# Durchgangspr_fer11.net
KiCad netlist of a schematic drawn in EAGLE
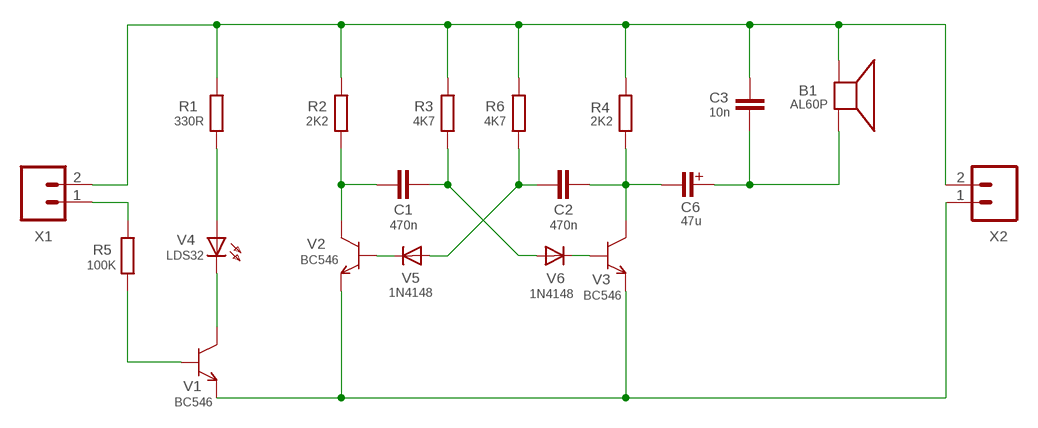
[diagram p0: schematic, sheet 1]

(export (version "E")
  (design (tool "Eeschema 10.0.6"))
  (components
    (comp (ref "B1")
      (value "AL60P")
      (footprint "eagle-import:AL60P")
      (libsource (lib "eagle-import") (part "AL60P"))
    )
    (comp (ref "C1")
      (value "470n")
      (footprint "eagle-import:C050-024X044")
      (libsource (lib "eagle-import") (part "C-EUC05-024X044"))
    )
    (comp (ref "C2")
      (value "470n")
      (footprint "eagle-import:C050-024X044")
      (libsource (lib "eagle-import") (part "C-EUC05-024X044"))
    )
    (comp (ref "C3")
      (value "10n")
      (footprint "eagle-import:C050-024X044")
      (libsource (lib "eagle-import") (part "C-EUC05-024X044"))
    )
    (comp (ref "C6")
      (value "47u")
      (footprint "eagle-import:E2,5-6")
      (libsource (lib "eagle-import") (part "CPOL-EUE2.5-6"))
    )
    (comp (ref "R1")
      (value "330R")
      (footprint "eagle-import:0207_10")
      (libsource (lib "eagle-import") (part "R-EU_0207/10"))
    )
    (comp (ref "R2")
      (value "2K2")
      (footprint "eagle-import:0207_10")
      (libsource (lib "eagle-import") (part "R-EU_0207/10"))
    )
    (comp (ref "R3")
      (value "4K7")
      (footprint "eagle-import:0207_10")
      (libsource (lib "eagle-import") (part "R-EU_0207/10"))
    )
    (comp (ref "R4")
      (value "2K2")
      (footprint "eagle-import:0207_10")
      (libsource (lib "eagle-import") (part "R-EU_0207/10"))
    )
    (comp (ref "R5")
      (value "100K")
      (footprint "eagle-import:0207_10")
      (libsource (lib "eagle-import") (part "R-EU_0207/10"))
    )
    (comp (ref "R6")
      (value "4K7")
      (footprint "eagle-import:0207_10")
      (libsource (lib "eagle-import") (part "R-EU_0207/10"))
    )
    (comp (ref "V1")
      (value "BC546")
      (footprint "eagle-import:TO92IL")
      (libsource (lib "eagle-import") (part "NPN_EBCBC546"))
    )
    (comp (ref "V2")
      (value "BC546")
      (footprint "eagle-import:TO92IL")
      (libsource (lib "eagle-import") (part "NPN_EBCBC546"))
    )
    (comp (ref "V3")
      (value "BC546")
      (footprint "eagle-import:TO92IL")
      (libsource (lib "eagle-import") (part "NPN_EBCBC546"))
    )
    (comp (ref "V4")
      (value "LDS32")
      (footprint "eagle-import:LED5")
      (libsource (lib "eagle-import") (part "LED5MM"))
    )
    (comp (ref "V5")
      (value "1N4148")
      (footprint "eagle-import:D7_5")
      (libsource (lib "eagle-import") (part "DIODE7_5"))
    )
    (comp (ref "V6")
      (value "1N4148")
      (footprint "eagle-import:D7_5")
      (libsource (lib "eagle-import") (part "DIODE7_5"))
    )
    (comp (ref "X1")
      (value "M02")
      (footprint "eagle-import:02P")
      (libsource (lib "eagle-import") (part "M02"))
    )
    (comp (ref "X2")
      (value "M02")
      (footprint "eagle-import:02P")
      (libsource (lib "eagle-import") (part "M02"))
    )
  )
  (nets
    (net (code "1") (name "Net-(B1-Pad1)") (class "Default")
      (node (ref "B1") (pin "1") (pinfunction "1_1") (pintype "passive"))
      (node (ref "C3") (pin "1") (pinfunction "1_1") (pintype "passive"))
      (node (ref "R1") (pin "2") (pinfunction "2_2") (pintype "passive"))
      (node (ref "R2") (pin "2") (pinfunction "2_2") (pintype "passive"))
      (node (ref "R3") (pin "2") (pinfunction "2_2") (pintype "passive"))
      (node (ref "R4") (pin "2") (pinfunction "2_2") (pintype "passive"))
      (node (ref "R6") (pin "2") (pinfunction "2_2") (pintype "passive"))
      (node (ref "X1") (pin "2") (pinfunction "2_2") (pintype "passive"))
      (node (ref "X2") (pin "2") (pinfunction "2_2") (pintype "passive"))
    )
    (net (code "2") (name "Net-(B1-Pad2)") (class "Default")
      (node (ref "B1") (pin "2") (pinfunction "2_2") (pintype "passive"))
      (node (ref "C3") (pin "2") (pinfunction "2_2") (pintype "passive"))
      (node (ref "C6") (pin "+") (pinfunction "+_+") (pintype "passive"))
    )
    (net (code "3") (name "Net-(C1-Pad1)") (class "Default")
      (node (ref "C1") (pin "1") (pinfunction "1_1") (pintype "passive"))
      (node (ref "R2") (pin "1") (pinfunction "1_1") (pintype "passive"))
      (node (ref "V2") (pin "C") (pinfunction "C_C") (pintype "passive"))
    )
    (net (code "4") (name "Net-(C1-Pad2)") (class "Default")
      (node (ref "C1") (pin "2") (pinfunction "2_2") (pintype "passive"))
      (node (ref "R3") (pin "1") (pinfunction "1_1") (pintype "passive"))
      (node (ref "V6") (pin "A") (pinfunction "A_A") (pintype "passive"))
    )
    (net (code "5") (name "Net-(C2-Pad1)") (class "Default")
      (node (ref "C2") (pin "1") (pinfunction "1_1") (pintype "passive"))
      (node (ref "R6") (pin "1") (pinfunction "1_1") (pintype "passive"))
      (node (ref "V5") (pin "A") (pinfunction "A_A") (pintype "passive"))
    )
    (net (code "6") (name "Net-(C2-Pad2)") (class "Default")
      (node (ref "C2") (pin "2") (pinfunction "2_2") (pintype "passive"))
      (node (ref "C6") (pin "-") (pinfunction "-_-") (pintype "passive"))
      (node (ref "R4") (pin "1") (pinfunction "1_1") (pintype "passive"))
      (node (ref "V3") (pin "C") (pinfunction "C_C") (pintype "passive"))
    )
    (net (code "7") (name "Net-(R1-Pad1)") (class "Default")
      (node (ref "R1") (pin "1") (pinfunction "1_1") (pintype "passive"))
      (node (ref "V4") (pin "A") (pinfunction "A_A") (pintype "passive"))
    )
    (net (code "8") (name "Net-(R5-Pad1)") (class "Default")
      (node (ref "R5") (pin "1") (pinfunction "1_1") (pintype "passive"))
      (node (ref "X1") (pin "1") (pinfunction "1_1") (pintype "passive"))
    )
    (net (code "9") (name "Net-(R5-Pad2)") (class "Default")
      (node (ref "R5") (pin "2") (pinfunction "2_2") (pintype "passive"))
      (node (ref "V1") (pin "B") (pinfunction "B_B") (pintype "passive"))
    )
    (net (code "10") (name "Net-(V1-PadE)") (class "Default")
      (node (ref "V1") (pin "E") (pinfunction "E_E") (pintype "passive"))
      (node (ref "V2") (pin "E") (pinfunction "E_E") (pintype "passive"))
      (node (ref "V3") (pin "E") (pinfunction "E_E") (pintype "passive"))
      (node (ref "X2") (pin "1") (pinfunction "1_1") (pintype "passive"))
    )
    (net (code "11") (name "Net-(V2-PadB)") (class "Default")
      (node (ref "V2") (pin "B") (pinfunction "B_B") (pintype "passive"))
      (node (ref "V5") (pin "C") (pinfunction "C_C") (pintype "passive"))
    )
    (net (code "12") (name "Net-(V3-PadB)") (class "Default")
      (node (ref "V3") (pin "B") (pinfunction "B_B") (pintype "passive"))
      (node (ref "V6") (pin "C") (pinfunction "C_C") (pintype "passive"))
    )
    (net (code "13") (name "Net-(V4-C)") (class "Default")
      (node (ref "V1") (pin "C") (pinfunction "C_C") (pintype "passive"))
      (node (ref "V4") (pin "K") (pinfunction "C_K") (pintype "passive"))
    )
  )
)
